# LTC6811_slave_12s_rev4.net
KiCad netlist of a schematic drawn in EAGLE
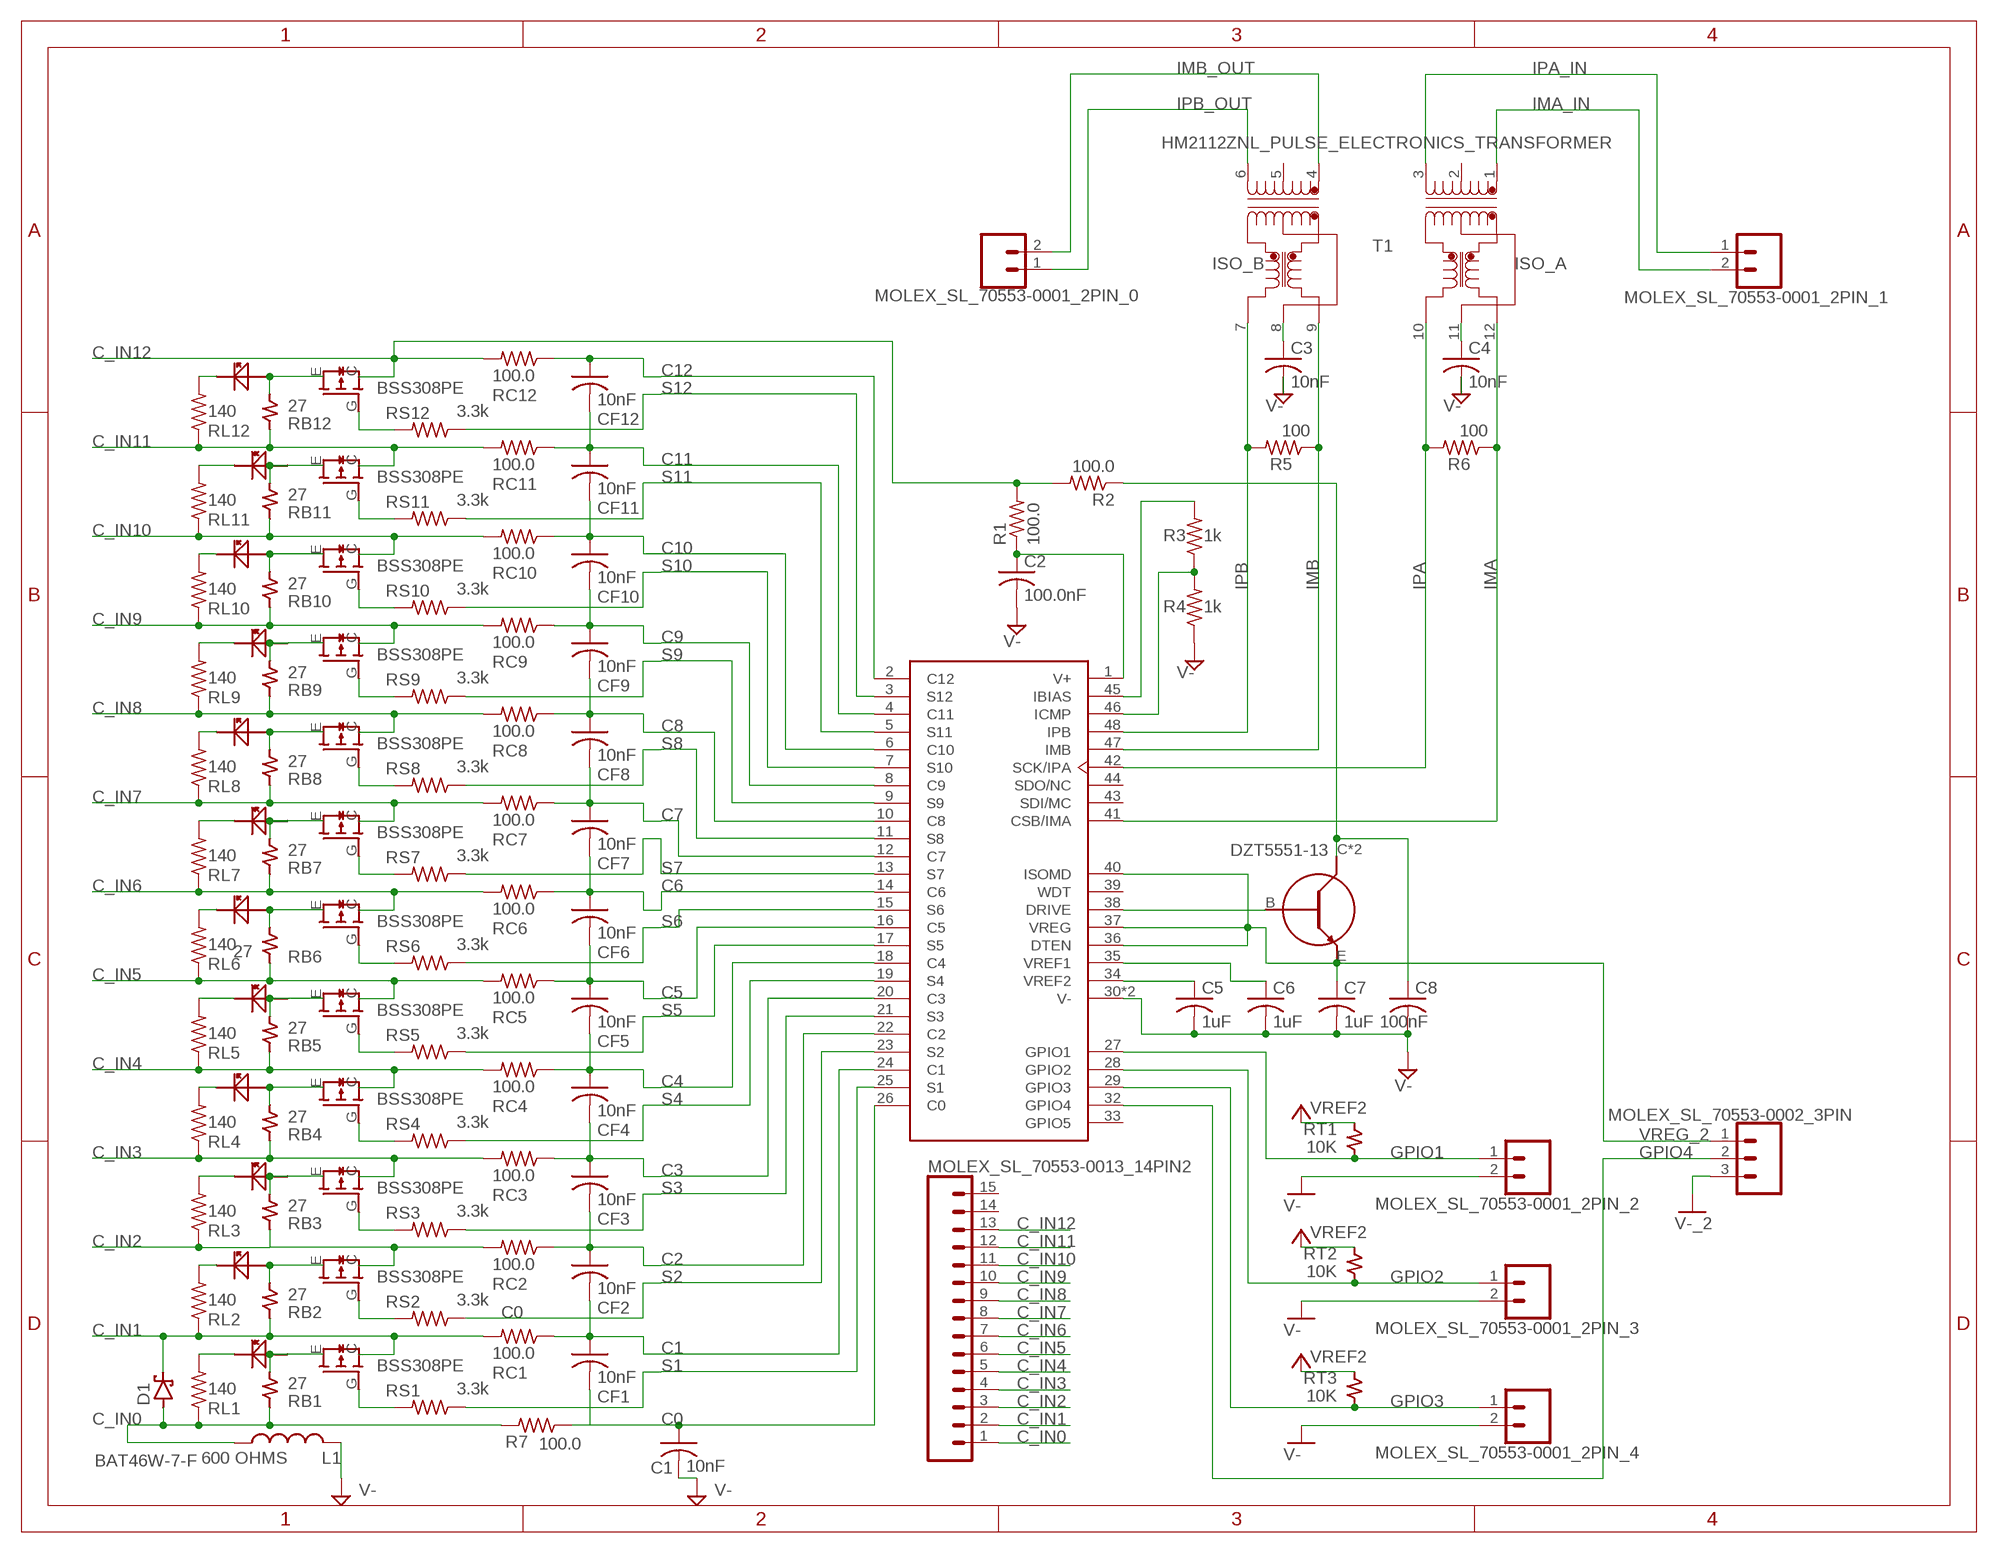
[diagram p0: schematic, sheet 1]

(export (version "E")
  (design (tool "Eeschema 10.0.6"))
  (components
    (comp (ref "C1")
      (value "10nF")
      (footprint "eagle-import:C0805")
      (libsource (lib "eagle-import") (part "C-USC0805"))
    )
    (comp (ref "C2")
      (value "100.0nF")
      (footprint "eagle-import:C0805")
      (libsource (lib "eagle-import") (part "C-USC0805"))
    )
    (comp (ref "C3")
      (value "10nF")
      (footprint "eagle-import:C0805")
      (libsource (lib "eagle-import") (part "C-USC0805"))
    )
    (comp (ref "C4")
      (value "10nF")
      (footprint "eagle-import:C0805")
      (libsource (lib "eagle-import") (part "C-USC0805"))
    )
    (comp (ref "C5")
      (value "1uF")
      (footprint "eagle-import:C0805")
      (libsource (lib "eagle-import") (part "C-USC0805"))
    )
    (comp (ref "C6")
      (value "1uF")
      (footprint "eagle-import:C0805")
      (libsource (lib "eagle-import") (part "C-USC0805"))
    )
    (comp (ref "C7")
      (value "1uF")
      (footprint "eagle-import:C0805")
      (libsource (lib "eagle-import") (part "C-USC0805"))
    )
    (comp (ref "C8")
      (value "100nF")
      (footprint "eagle-import:C0805")
      (libsource (lib "eagle-import") (part "C-USC0805"))
    )
    (comp (ref "CF1")
      (value "10nF")
      (footprint "eagle-import:C0805")
      (libsource (lib "eagle-import") (part "C-USC0805"))
    )
    (comp (ref "CF2")
      (value "10nF")
      (footprint "eagle-import:C0805")
      (libsource (lib "eagle-import") (part "C-USC0805"))
    )
    (comp (ref "CF3")
      (value "10nF")
      (footprint "eagle-import:C0805")
      (libsource (lib "eagle-import") (part "C-USC0805"))
    )
    (comp (ref "CF4")
      (value "10nF")
      (footprint "eagle-import:C0805")
      (libsource (lib "eagle-import") (part "C-USC0805"))
    )
    (comp (ref "CF5")
      (value "10nF")
      (footprint "eagle-import:C0805")
      (libsource (lib "eagle-import") (part "C-USC0805"))
    )
    (comp (ref "CF6")
      (value "10nF")
      (footprint "eagle-import:C0805")
      (libsource (lib "eagle-import") (part "C-USC0805"))
    )
    (comp (ref "CF7")
      (value "10nF")
      (footprint "eagle-import:C0805")
      (libsource (lib "eagle-import") (part "C-USC0805"))
    )
    (comp (ref "CF8")
      (value "10nF")
      (footprint "eagle-import:C0805")
      (libsource (lib "eagle-import") (part "C-USC0805"))
    )
    (comp (ref "CF9")
      (value "10nF")
      (footprint "eagle-import:C0805")
      (libsource (lib "eagle-import") (part "C-USC0805"))
    )
    (comp (ref "CF10")
      (value "10nF")
      (footprint "eagle-import:C0805")
      (libsource (lib "eagle-import") (part "C-USC0805"))
    )
    (comp (ref "CF11")
      (value "10nF")
      (footprint "eagle-import:C0805")
      (libsource (lib "eagle-import") (part "C-USC0805"))
    )
    (comp (ref "CF12")
      (value "10nF")
      (footprint "eagle-import:C0805")
      (libsource (lib "eagle-import") (part "C-USC0805"))
    )
    (comp (ref "D1")
      (value "BAT46W-7-F")
      (footprint "eagle-import:SOD123")
      (libsource (lib "eagle-import") (part "BAT46W-7-F"))
    )
    (comp (ref "L1")
      (value "600 OHMS")
      (footprint "eagle-import:0805_COMPONENT")
      (libsource (lib "eagle-import") (part "0805_FERRITEBEAD_INDUCTOR"))
    )
    (comp (ref "LED1")
      (value "LED_0805")
      (footprint "eagle-import:0805_COMPONENT")
      (libsource (lib "eagle-import") (part "LED_0805"))
    )
    (comp (ref "LED2")
      (value "LED_0805")
      (footprint "eagle-import:0805_COMPONENT")
      (libsource (lib "eagle-import") (part "LED_0805"))
    )
    (comp (ref "LED3")
      (value "LED_0805")
      (footprint "eagle-import:0805_COMPONENT")
      (libsource (lib "eagle-import") (part "LED_0805"))
    )
    (comp (ref "LED4")
      (value "LED_0805")
      (footprint "eagle-import:0805_COMPONENT")
      (libsource (lib "eagle-import") (part "LED_0805"))
    )
    (comp (ref "LED5")
      (value "LED_0805")
      (footprint "eagle-import:0805_COMPONENT")
      (libsource (lib "eagle-import") (part "LED_0805"))
    )
    (comp (ref "LED6")
      (value "LED_0805")
      (footprint "eagle-import:0805_COMPONENT")
      (libsource (lib "eagle-import") (part "LED_0805"))
    )
    (comp (ref "LED7")
      (value "LED_0805")
      (footprint "eagle-import:0805_COMPONENT")
      (libsource (lib "eagle-import") (part "LED_0805"))
    )
    (comp (ref "LED8")
      (value "LED_0805")
      (footprint "eagle-import:0805_COMPONENT")
      (libsource (lib "eagle-import") (part "LED_0805"))
    )
    (comp (ref "LED9")
      (value "LED_0805")
      (footprint "eagle-import:0805_COMPONENT")
      (libsource (lib "eagle-import") (part "LED_0805"))
    )
    (comp (ref "LED10")
      (value "LED_0805")
      (footprint "eagle-import:0805_COMPONENT")
      (libsource (lib "eagle-import") (part "LED_0805"))
    )
    (comp (ref "LED11")
      (value "LED_0805")
      (footprint "eagle-import:0805_COMPONENT")
      (libsource (lib "eagle-import") (part "LED_0805"))
    )
    (comp (ref "LED12")
      (value "LED_0805")
      (footprint "eagle-import:0805_COMPONENT")
      (libsource (lib "eagle-import") (part "LED_0805"))
    )
    (comp (ref "MOLEX_SL_70553-0001_2PIN_0")
      (value "CONN_02")
      (footprint "eagle-import:1X02")
      (libsource (lib "eagle-import") (part "CONN_02"))
    )
    (comp (ref "MOLEX_SL_70553-0001_2PIN_1")
      (value "CONN_02")
      (footprint "eagle-import:1X02")
      (libsource (lib "eagle-import") (part "CONN_02"))
    )
    (comp (ref "MOLEX_SL_70553-0001_2PIN_2")
      (value "CONN_02")
      (footprint "eagle-import:1X02")
      (libsource (lib "eagle-import") (part "CONN_02"))
    )
    (comp (ref "MOLEX_SL_70553-0001_2PIN_3")
      (value "CONN_02")
      (footprint "eagle-import:1X02")
      (libsource (lib "eagle-import") (part "CONN_02"))
    )
    (comp (ref "MOLEX_SL_70553-0001_2PIN_4")
      (value "CONN_02")
      (footprint "eagle-import:1X02")
      (libsource (lib "eagle-import") (part "CONN_02"))
    )
    (comp (ref "MOLEX_SL_70553-0002_3PIN")
      (value "CONN_03")
      (footprint "eagle-import:1X03")
      (libsource (lib "eagle-import") (part "CONN_03"))
    )
    (comp (ref "MOLEX_SL_70553-0013_14PIN2")
      (value "CONN_15")
      (footprint "eagle-import:1X15")
      (libsource (lib "eagle-import") (part "CONN_15"))
    )
    (comp (ref "R1")
      (value "100.0")
      (footprint "eagle-import:R0805")
      (libsource (lib "eagle-import") (part "R-US_R0805"))
    )
    (comp (ref "R2")
      (value "100.0")
      (footprint "eagle-import:R0805")
      (libsource (lib "eagle-import") (part "R-US_R0805"))
    )
    (comp (ref "R3")
      (value "1k")
      (footprint "eagle-import:R0805")
      (libsource (lib "eagle-import") (part "R-US_R0805"))
    )
    (comp (ref "R4")
      (value "1k")
      (footprint "eagle-import:R0805")
      (libsource (lib "eagle-import") (part "R-US_R0805"))
    )
    (comp (ref "R5")
      (value "100")
      (footprint "eagle-import:R0805")
      (libsource (lib "eagle-import") (part "R-US_R0805"))
    )
    (comp (ref "R6")
      (value "100")
      (footprint "eagle-import:R0805")
      (libsource (lib "eagle-import") (part "R-US_R0805"))
    )
    (comp (ref "R7")
      (value "100.0")
      (footprint "eagle-import:R0805")
      (libsource (lib "eagle-import") (part "R-US_R0805"))
    )
    (comp (ref "RB1")
      (value "27")
      (footprint "eagle-import:2817_COMPONENT")
      (libsource (lib "eagle-import") (part "2817_RESISTOR"))
    )
    (comp (ref "RB2")
      (value "27")
      (footprint "eagle-import:2817_COMPONENT")
      (libsource (lib "eagle-import") (part "2817_RESISTOR"))
    )
    (comp (ref "RB3")
      (value "27")
      (footprint "eagle-import:2817_COMPONENT")
      (libsource (lib "eagle-import") (part "2817_RESISTOR"))
    )
    (comp (ref "RB4")
      (value "27")
      (footprint "eagle-import:2817_COMPONENT")
      (libsource (lib "eagle-import") (part "2817_RESISTOR"))
    )
    (comp (ref "RB5")
      (value "27")
      (footprint "eagle-import:2817_COMPONENT")
      (libsource (lib "eagle-import") (part "2817_RESISTOR"))
    )
    (comp (ref "RB6")
      (value "27")
      (footprint "eagle-import:2817_COMPONENT")
      (libsource (lib "eagle-import") (part "2817_RESISTOR"))
    )
    (comp (ref "RB7")
      (value "27")
      (footprint "eagle-import:2817_COMPONENT")
      (libsource (lib "eagle-import") (part "2817_RESISTOR"))
    )
    (comp (ref "RB8")
      (value "27")
      (footprint "eagle-import:2817_COMPONENT")
      (libsource (lib "eagle-import") (part "2817_RESISTOR"))
    )
    (comp (ref "RB9")
      (value "27")
      (footprint "eagle-import:2817_COMPONENT")
      (libsource (lib "eagle-import") (part "2817_RESISTOR"))
    )
    (comp (ref "RB10")
      (value "27")
      (footprint "eagle-import:2817_COMPONENT")
      (libsource (lib "eagle-import") (part "2817_RESISTOR"))
    )
    (comp (ref "RB11")
      (value "27")
      (footprint "eagle-import:2817_COMPONENT")
      (libsource (lib "eagle-import") (part "2817_RESISTOR"))
    )
    (comp (ref "RB12")
      (value "27")
      (footprint "eagle-import:2817_COMPONENT")
      (libsource (lib "eagle-import") (part "2817_RESISTOR"))
    )
    (comp (ref "RC1")
      (value "100.0")
      (footprint "eagle-import:R0805")
      (libsource (lib "eagle-import") (part "R-US_R0805"))
    )
    (comp (ref "RC2")
      (value "100.0")
      (footprint "eagle-import:R0805")
      (libsource (lib "eagle-import") (part "R-US_R0805"))
    )
    (comp (ref "RC3")
      (value "100.0")
      (footprint "eagle-import:R0805")
      (libsource (lib "eagle-import") (part "R-US_R0805"))
    )
    (comp (ref "RC4")
      (value "100.0")
      (footprint "eagle-import:R0805")
      (libsource (lib "eagle-import") (part "R-US_R0805"))
    )
    (comp (ref "RC5")
      (value "100.0")
      (footprint "eagle-import:R0805")
      (libsource (lib "eagle-import") (part "R-US_R0805"))
    )
    (comp (ref "RC6")
      (value "100.0")
      (footprint "eagle-import:R0805")
      (libsource (lib "eagle-import") (part "R-US_R0805"))
    )
    (comp (ref "RC7")
      (value "100.0")
      (footprint "eagle-import:R0805")
      (libsource (lib "eagle-import") (part "R-US_R0805"))
    )
    (comp (ref "RC8")
      (value "100.0")
      (footprint "eagle-import:R0805")
      (libsource (lib "eagle-import") (part "R-US_R0805"))
    )
    (comp (ref "RC9")
      (value "100.0")
      (footprint "eagle-import:R0805")
      (libsource (lib "eagle-import") (part "R-US_R0805"))
    )
    (comp (ref "RC10")
      (value "100.0")
      (footprint "eagle-import:R0805")
      (libsource (lib "eagle-import") (part "R-US_R0805"))
    )
    (comp (ref "RC11")
      (value "100.0")
      (footprint "eagle-import:R0805")
      (libsource (lib "eagle-import") (part "R-US_R0805"))
    )
    (comp (ref "RC12")
      (value "100.0")
      (footprint "eagle-import:R0805")
      (libsource (lib "eagle-import") (part "R-US_R0805"))
    )
    (comp (ref "RL1")
      (value "140")
      (footprint "eagle-import:R0805")
      (libsource (lib "eagle-import") (part "R-US_R0805"))
    )
    (comp (ref "RL2")
      (value "140")
      (footprint "eagle-import:R0805")
      (libsource (lib "eagle-import") (part "R-US_R0805"))
    )
    (comp (ref "RL3")
      (value "140")
      (footprint "eagle-import:R0805")
      (libsource (lib "eagle-import") (part "R-US_R0805"))
    )
    (comp (ref "RL4")
      (value "140")
      (footprint "eagle-import:R0805")
      (libsource (lib "eagle-import") (part "R-US_R0805"))
    )
    (comp (ref "RL5")
      (value "140")
      (footprint "eagle-import:R0805")
      (libsource (lib "eagle-import") (part "R-US_R0805"))
    )
    (comp (ref "RL6")
      (value "140")
      (footprint "eagle-import:R0805")
      (libsource (lib "eagle-import") (part "R-US_R0805"))
    )
    (comp (ref "RL7")
      (value "140")
      (footprint "eagle-import:R0805")
      (libsource (lib "eagle-import") (part "R-US_R0805"))
    )
    (comp (ref "RL8")
      (value "140")
      (footprint "eagle-import:R0805")
      (libsource (lib "eagle-import") (part "R-US_R0805"))
    )
    (comp (ref "RL9")
      (value "140")
      (footprint "eagle-import:R0805")
      (libsource (lib "eagle-import") (part "R-US_R0805"))
    )
    (comp (ref "RL10")
      (value "140")
      (footprint "eagle-import:R0805")
      (libsource (lib "eagle-import") (part "R-US_R0805"))
    )
    (comp (ref "RL11")
      (value "140")
      (footprint "eagle-import:R0805")
      (libsource (lib "eagle-import") (part "R-US_R0805"))
    )
    (comp (ref "RL12")
      (value "140")
      (footprint "eagle-import:R0805")
      (libsource (lib "eagle-import") (part "R-US_R0805"))
    )
    (comp (ref "RS1")
      (value "3.3k")
      (footprint "eagle-import:R0805")
      (libsource (lib "eagle-import") (part "R-US_R0805"))
    )
    (comp (ref "RS2")
      (value "3.3k")
      (footprint "eagle-import:R0805")
      (libsource (lib "eagle-import") (part "R-US_R0805"))
    )
    (comp (ref "RS3")
      (value "3.3k")
      (footprint "eagle-import:R0805")
      (libsource (lib "eagle-import") (part "R-US_R0805"))
    )
    (comp (ref "RS4")
      (value "3.3k")
      (footprint "eagle-import:R0805")
      (libsource (lib "eagle-import") (part "R-US_R0805"))
    )
    (comp (ref "RS5")
      (value "3.3k")
      (footprint "eagle-import:R0805")
      (libsource (lib "eagle-import") (part "R-US_R0805"))
    )
    (comp (ref "RS6")
      (value "3.3k")
      (footprint "eagle-import:R0805")
      (libsource (lib "eagle-import") (part "R-US_R0805"))
    )
    (comp (ref "RS7")
      (value "3.3k")
      (footprint "eagle-import:R0805")
      (libsource (lib "eagle-import") (part "R-US_R0805"))
    )
    (comp (ref "RS8")
      (value "3.3k")
      (footprint "eagle-import:R0805")
      (libsource (lib "eagle-import") (part "R-US_R0805"))
    )
    (comp (ref "RS9")
      (value "3.3k")
      (footprint "eagle-import:R0805")
      (libsource (lib "eagle-import") (part "R-US_R0805"))
    )
    (comp (ref "RS10")
      (value "3.3k")
      (footprint "eagle-import:R0805")
      (libsource (lib "eagle-import") (part "R-US_R0805"))
    )
    (comp (ref "RS11")
      (value "3.3k")
      (footprint "eagle-import:R0805")
      (libsource (lib "eagle-import") (part "R-US_R0805"))
    )
    (comp (ref "RS12")
      (value "3.3k")
      (footprint "eagle-import:R0805")
      (libsource (lib "eagle-import") (part "R-US_R0805"))
    )
    (comp (ref "RT1")
      (value "10K")
      (footprint "eagle-import:0805_RESISTOR")
      (libsource (lib "eagle-import") (part "0805_RESISTOR"))
    )
    (comp (ref "RT2")
      (value "10K")
      (footprint "eagle-import:0805_RESISTOR")
      (libsource (lib "eagle-import") (part "0805_RESISTOR"))
    )
    (comp (ref "RT3")
      (value "10K")
      (footprint "eagle-import:0805_RESISTOR")
      (libsource (lib "eagle-import") (part "0805_RESISTOR"))
    )
    (comp (ref "SW1")
      (value "BSS308PEH6327")
      (footprint "eagle-import:SOT23")
      (libsource (lib "eagle-import") (part "BSS308PEH6327"))
    )
    (comp (ref "SW2")
      (value "BSS308PEH6327")
      (footprint "eagle-import:SOT23")
      (libsource (lib "eagle-import") (part "BSS308PEH6327"))
    )
    (comp (ref "SW3")
      (value "BSS308PEH6327")
      (footprint "eagle-import:SOT23")
      (libsource (lib "eagle-import") (part "BSS308PEH6327"))
    )
    (comp (ref "SW4")
      (value "BSS308PEH6327")
      (footprint "eagle-import:SOT23")
      (libsource (lib "eagle-import") (part "BSS308PEH6327"))
    )
    (comp (ref "SW5")
      (value "BSS308PEH6327")
      (footprint "eagle-import:SOT23")
      (libsource (lib "eagle-import") (part "BSS308PEH6327"))
    )
    (comp (ref "SW6")
      (value "BSS308PEH6327")
      (footprint "eagle-import:SOT23")
      (libsource (lib "eagle-import") (part "BSS308PEH6327"))
    )
    (comp (ref "SW7")
      (value "BSS308PEH6327")
      (footprint "eagle-import:SOT23")
      (libsource (lib "eagle-import") (part "BSS308PEH6327"))
    )
    (comp (ref "SW8")
      (value "BSS308PEH6327")
      (footprint "eagle-import:SOT23")
      (libsource (lib "eagle-import") (part "BSS308PEH6327"))
    )
    (comp (ref "SW9")
      (value "BSS308PEH6327")
      (footprint "eagle-import:SOT23")
      (libsource (lib "eagle-import") (part "BSS308PEH6327"))
    )
    (comp (ref "SW10")
      (value "BSS308PEH6327")
      (footprint "eagle-import:SOT23")
      (libsource (lib "eagle-import") (part "BSS308PEH6327"))
    )
    (comp (ref "SW11")
      (value "BSS308PEH6327")
      (footprint "eagle-import:SOT23")
      (libsource (lib "eagle-import") (part "BSS308PEH6327"))
    )
    (comp (ref "SW12")
      (value "BSS308PEH6327")
      (footprint "eagle-import:SOT23")
      (libsource (lib "eagle-import") (part "BSS308PEH6327"))
    )
    (comp (ref "SW13")
      (value "DZT5551-13")
      (footprint "eagle-import:SOT223-4")
      (libsource (lib "eagle-import") (part "DZT5551-13"))
    )
    (comp (ref "U$3")
      (value "HM2112ZNL_PULSE_ELECTRONICS_TRANSFORMER")
      (footprint "eagle-import:HM2112ZNL_12SMT")
      (libsource (lib "eagle-import") (part "HM2112ZNL_PULSE_ELECTRONICS_TRANSFORMER"))
    )
    (comp (ref "U1")
      (value "LTC6811HG-2#PBF")
      (footprint "eagle-import:LTC6811-1")
      (fields (field (name "MF") "Linear Technology/Analog"))
      (libsource (lib "eagle-import") (part "LTC6811HG-2#PBF"))
    )
  )
  (nets
    (net (code "1") (name "/C0") (class "Default")
      (node (ref "C1") (pin "1") (pinfunction "1_1") (pintype "passive"))
      (node (ref "R7") (pin "1") (pinfunction "1_1") (pintype "passive"))
      (node (ref "U1") (pin "26") (pinfunction "C0_26") (pintype "input"))
    )
    (net (code "2") (name "/C1") (class "Default")
      (node (ref "CF1") (pin "1") (pinfunction "1_1") (pintype "passive"))
      (node (ref "CF2") (pin "2") (pinfunction "2_2") (pintype "passive"))
      (node (ref "RC1") (pin "1") (pinfunction "1_1") (pintype "passive"))
      (node (ref "U1") (pin "24") (pinfunction "C1_24") (pintype "input"))
    )
    (net (code "3") (name "/C2") (class "Default")
      (node (ref "CF2") (pin "1") (pinfunction "1_1") (pintype "passive"))
      (node (ref "CF3") (pin "2") (pinfunction "2_2") (pintype "passive"))
      (node (ref "RC2") (pin "1") (pinfunction "1_1") (pintype "passive"))
      (node (ref "U1") (pin "22") (pinfunction "C2_22") (pintype "input"))
    )
    (net (code "4") (name "/C3") (class "Default")
      (node (ref "CF3") (pin "1") (pinfunction "1_1") (pintype "passive"))
      (node (ref "CF4") (pin "2") (pinfunction "2_2") (pintype "passive"))
      (node (ref "RC3") (pin "1") (pinfunction "1_1") (pintype "passive"))
      (node (ref "U1") (pin "20") (pinfunction "C3_20") (pintype "input"))
    )
    (net (code "5") (name "/C4") (class "Default")
      (node (ref "CF4") (pin "1") (pinfunction "1_1") (pintype "passive"))
      (node (ref "CF5") (pin "2") (pinfunction "2_2") (pintype "passive"))
      (node (ref "RC4") (pin "1") (pinfunction "1_1") (pintype "passive"))
      (node (ref "U1") (pin "18") (pinfunction "C4_18") (pintype "input"))
    )
    (net (code "6") (name "/C5") (class "Default")
      (node (ref "CF5") (pin "1") (pinfunction "1_1") (pintype "passive"))
      (node (ref "CF6") (pin "2") (pinfunction "2_2") (pintype "passive"))
      (node (ref "RC5") (pin "1") (pinfunction "1_1") (pintype "passive"))
      (node (ref "U1") (pin "16") (pinfunction "C5_16") (pintype "input"))
    )
    (net (code "7") (name "/C6") (class "Default")
      (node (ref "CF6") (pin "1") (pinfunction "1_1") (pintype "passive"))
      (node (ref "CF7") (pin "2") (pinfunction "2_2") (pintype "passive"))
      (node (ref "RC6") (pin "1") (pinfunction "1_1") (pintype "passive"))
      (node (ref "U1") (pin "14") (pinfunction "C6_14") (pintype "input"))
    )
    (net (code "8") (name "/C7") (class "Default")
      (node (ref "CF7") (pin "1") (pinfunction "1_1") (pintype "passive"))
      (node (ref "CF8") (pin "2") (pinfunction "2_2") (pintype "passive"))
      (node (ref "RC7") (pin "1") (pinfunction "1_1") (pintype "passive"))
      (node (ref "U1") (pin "12") (pinfunction "C7_12") (pintype "input"))
    )
    (net (code "9") (name "/C8") (class "Default")
      (node (ref "CF8") (pin "1") (pinfunction "1_1") (pintype "passive"))
      (node (ref "CF9") (pin "2") (pinfunction "2_2") (pintype "passive"))
      (node (ref "RC8") (pin "1") (pinfunction "1_1") (pintype "passive"))
      (node (ref "U1") (pin "10") (pinfunction "C8_10") (pintype "input"))
    )
    (net (code "10") (name "/C9") (class "Default")
      (node (ref "CF10") (pin "2") (pinfunction "2_2") (pintype "passive"))
      (node (ref "CF9") (pin "1") (pinfunction "1_1") (pintype "passive"))
      (node (ref "RC9") (pin "1") (pinfunction "1_1") (pintype "passive"))
      (node (ref "U1") (pin "8") (pinfunction "C9_8") (pintype "input"))
    )
    (net (code "11") (name "/C10") (class "Default")
      (node (ref "CF10") (pin "1") (pinfunction "1_1") (pintype "passive"))
      (node (ref "CF11") (pin "2") (pinfunction "2_2") (pintype "passive"))
      (node (ref "RC10") (pin "1") (pinfunction "1_1") (pintype "passive"))
      (node (ref "U1") (pin "6") (pinfunction "C10_6") (pintype "input"))
    )
    (net (code "12") (name "/C11") (class "Default")
      (node (ref "CF11") (pin "1") (pinfunction "1_1") (pintype "passive"))
      (node (ref "CF12") (pin "2") (pinfunction "2_2") (pintype "passive"))
      (node (ref "RC11") (pin "1") (pinfunction "1_1") (pintype "passive"))
      (node (ref "U1") (pin "4") (pinfunction "C11_4") (pintype "input"))
    )
    (net (code "13") (name "/C12") (class "Default")
      (node (ref "CF12") (pin "1") (pinfunction "1_1") (pintype "passive"))
      (node (ref "RC12") (pin "1") (pinfunction "1_1") (pintype "passive"))
      (node (ref "U1") (pin "2") (pinfunction "C12_2") (pintype "input"))
    )
    (net (code "14") (name "/C_IN0") (class "Default")
      (node (ref "D1") (pin "A") (pinfunction "A_A") (pintype "passive"))
      (node (ref "L1") (pin "1") (pinfunction "1_1") (pintype "passive"))
      (node (ref "MOLEX_SL_70553-0013_14PIN2") (pin "1") (pinfunction "1_1") (pintype "passive"))
      (node (ref "R7") (pin "2") (pinfunction "2_2") (pintype "passive"))
      (node (ref "RB1") (pin "2") (pinfunction "P$2_2") (pintype "bidirectional"))
      (node (ref "RL1") (pin "1") (pinfunction "1_1") (pintype "passive"))
    )
    (net (code "15") (name "/C_IN1") (class "Default")
      (node (ref "D1") (pin "C") (pinfunction "C_C") (pintype "passive"))
      (node (ref "MOLEX_SL_70553-0013_14PIN2") (pin "2") (pinfunction "2_2") (pintype "passive"))
      (node (ref "RB2") (pin "2") (pinfunction "P$2_2") (pintype "bidirectional"))
      (node (ref "RC1") (pin "2") (pinfunction "2_2") (pintype "passive"))
      (node (ref "RL2") (pin "1") (pinfunction "1_1") (pintype "passive"))
      (node (ref "SW1") (pin "C") (pinfunction "C_C") (pintype "bidirectional"))
    )
    (net (code "16") (name "/C_IN2") (class "Default")
      (node (ref "MOLEX_SL_70553-0013_14PIN2") (pin "3") (pinfunction "3_3") (pintype "passive"))
      (node (ref "RB3") (pin "2") (pinfunction "P$2_2") (pintype "bidirectional"))
      (node (ref "RC2") (pin "2") (pinfunction "2_2") (pintype "passive"))
      (node (ref "RL3") (pin "1") (pinfunction "1_1") (pintype "passive"))
      (node (ref "SW2") (pin "C") (pinfunction "C_C") (pintype "bidirectional"))
    )
    (net (code "17") (name "/C_IN3") (class "Default")
      (node (ref "MOLEX_SL_70553-0013_14PIN2") (pin "4") (pinfunction "4_4") (pintype "passive"))
      (node (ref "RB4") (pin "2") (pinfunction "P$2_2") (pintype "bidirectional"))
      (node (ref "RC3") (pin "2") (pinfunction "2_2") (pintype "passive"))
      (node (ref "RL4") (pin "1") (pinfunction "1_1") (pintype "passive"))
      (node (ref "SW3") (pin "C") (pinfunction "C_C") (pintype "bidirectional"))
    )
    (net (code "18") (name "/C_IN4") (class "Default")
      (node (ref "MOLEX_SL_70553-0013_14PIN2") (pin "5") (pinfunction "5_5") (pintype "passive"))
      (node (ref "RB5") (pin "2") (pinfunction "P$2_2") (pintype "bidirectional"))
      (node (ref "RC4") (pin "2") (pinfunction "2_2") (pintype "passive"))
      (node (ref "RL5") (pin "1") (pinfunction "1_1") (pintype "passive"))
      (node (ref "SW4") (pin "C") (pinfunction "C_C") (pintype "bidirectional"))
    )
    (net (code "19") (name "/C_IN5") (class "Default")
      (node (ref "MOLEX_SL_70553-0013_14PIN2") (pin "6") (pinfunction "6_6") (pintype "passive"))
      (node (ref "RB6") (pin "2") (pinfunction "P$2_2") (pintype "bidirectional"))
      (node (ref "RC5") (pin "2") (pinfunction "2_2") (pintype "passive"))
      (node (ref "RL6") (pin "1") (pinfunction "1_1") (pintype "passive"))
      (node (ref "SW5") (pin "C") (pinfunction "C_C") (pintype "bidirectional"))
    )
    (net (code "20") (name "/C_IN6") (class "Default")
      (node (ref "MOLEX_SL_70553-0013_14PIN2") (pin "7") (pinfunction "7_7") (pintype "passive"))
      (node (ref "RB7") (pin "2") (pinfunction "P$2_2") (pintype "bidirectional"))
      (node (ref "RC6") (pin "2") (pinfunction "2_2") (pintype "passive"))
      (node (ref "RL7") (pin "1") (pinfunction "1_1") (pintype "passive"))
      (node (ref "SW6") (pin "C") (pinfunction "C_C") (pintype "bidirectional"))
    )
    (net (code "21") (name "/C_IN7") (class "Default")
      (node (ref "MOLEX_SL_70553-0013_14PIN2") (pin "8") (pinfunction "8_8") (pintype "passive"))
      (node (ref "RB8") (pin "2") (pinfunction "P$2_2") (pintype "bidirectional"))
      (node (ref "RC7") (pin "2") (pinfunction "2_2") (pintype "passive"))
      (node (ref "RL8") (pin "1") (pinfunction "1_1") (pintype "passive"))
      (node (ref "SW7") (pin "C") (pinfunction "C_C") (pintype "bidirectional"))
    )
    (net (code "22") (name "/C_IN8") (class "Default")
      (node (ref "MOLEX_SL_70553-0013_14PIN2") (pin "9") (pinfunction "9_9") (pintype "passive"))
      (node (ref "RB9") (pin "2") (pinfunction "P$2_2") (pintype "bidirectional"))
      (node (ref "RC8") (pin "2") (pinfunction "2_2") (pintype "passive"))
      (node (ref "RL9") (pin "1") (pinfunction "1_1") (pintype "passive"))
      (node (ref "SW8") (pin "C") (pinfunction "C_C") (pintype "bidirectional"))
    )
    (net (code "23") (name "/C_IN9") (class "Default")
      (node (ref "MOLEX_SL_70553-0013_14PIN2") (pin "10") (pinfunction "10_10") (pintype "passive"))
      (node (ref "RB10") (pin "2") (pinfunction "P$2_2") (pintype "bidirectional"))
      (node (ref "RC9") (pin "2") (pinfunction "2_2") (pintype "passive"))
      (node (ref "RL10") (pin "1") (pinfunction "1_1") (pintype "passive"))
      (node (ref "SW9") (pin "C") (pinfunction "C_C") (pintype "bidirectional"))
    )
    (net (code "24") (name "/C_IN10") (class "Default")
      (node (ref "MOLEX_SL_70553-0013_14PIN2") (pin "11") (pinfunction "11_11") (pintype "passive"))
      (node (ref "RB11") (pin "2") (pinfunction "P$2_2") (pintype "bidirectional"))
      (node (ref "RC10") (pin "2") (pinfunction "2_2") (pintype "passive"))
      (node (ref "RL11") (pin "1") (pinfunction "1_1") (pintype "passive"))
      (node (ref "SW10") (pin "C") (pinfunction "C_C") (pintype "bidirectional"))
    )
    (net (code "25") (name "/C_IN11") (class "Default")
      (node (ref "MOLEX_SL_70553-0013_14PIN2") (pin "12") (pinfunction "12_12") (pintype "passive"))
      (node (ref "RB12") (pin "2") (pinfunction "P$2_2") (pintype "bidirectional"))
      (node (ref "RC11") (pin "2") (pinfunction "2_2") (pintype "passive"))
      (node (ref "RL12") (pin "1") (pinfunction "1_1") (pintype "passive"))
      (node (ref "SW11") (pin "C") (pinfunction "C_C") (pintype "bidirectional"))
    )
    (net (code "26") (name "/C_IN12") (class "Default")
      (node (ref "MOLEX_SL_70553-0013_14PIN2") (pin "13") (pinfunction "13_13") (pintype "passive"))
      (node (ref "R1") (pin "2") (pinfunction "2_2") (pintype "passive"))
      (node (ref "R2") (pin "2") (pinfunction "2_2") (pintype "passive"))
      (node (ref "RC12") (pin "2") (pinfunction "2_2") (pintype "passive"))
      (node (ref "SW12") (pin "C") (pinfunction "C_C") (pintype "bidirectional"))
    )
    (net (code "27") (name "/GPIO1") (class "Default")
      (node (ref "MOLEX_SL_70553-0001_2PIN_2") (pin "1") (pinfunction "1_1") (pintype "passive"))
      (node (ref "RT1") (pin "P$2") (pinfunction "P$2_P$2") (pintype "bidirectional"))
      (node (ref "U1") (pin "27") (pinfunction "GPIO1_27") (pintype "bidirectional"))
    )
    (net (code "28") (name "/GPIO2") (class "Default")
      (node (ref "MOLEX_SL_70553-0001_2PIN_3") (pin "1") (pinfunction "1_1") (pintype "passive"))
      (node (ref "RT2") (pin "P$2") (pinfunction "P$2_P$2") (pintype "bidirectional"))
      (node (ref "U1") (pin "28") (pinfunction "GPIO2_28") (pintype "bidirectional"))
    )
    (net (code "29") (name "/GPIO3") (class "Default")
      (node (ref "MOLEX_SL_70553-0001_2PIN_4") (pin "1") (pinfunction "1_1") (pintype "passive"))
      (node (ref "RT3") (pin "P$2") (pinfunction "P$2_P$2") (pintype "bidirectional"))
      (node (ref "U1") (pin "29") (pinfunction "GPIO3_29") (pintype "bidirectional"))
    )
    (net (code "30") (name "/GPIO4") (class "Default")
      (node (ref "MOLEX_SL_70553-0002_3PIN") (pin "2") (pinfunction "2_2") (pintype "passive"))
      (node (ref "U1") (pin "32") (pinfunction "GPIO4_32") (pintype "bidirectional"))
    )
    (net (code "31") (name "/IMA") (class "Default")
      (node (ref "R6") (pin "1") (pinfunction "1_1") (pintype "passive"))
      (node (ref "U$3") (pin "12") (pinfunction "12_12") (pintype "bidirectional"))
      (node (ref "U1") (pin "41") (pinfunction "CSB/IMA_41") (pintype "input"))
    )
    (net (code "32") (name "/IMA_IN") (class "Default")
      (node (ref "MOLEX_SL_70553-0001_2PIN_1") (pin "2") (pinfunction "2_2") (pintype "passive"))
      (node (ref "U$3") (pin "1") (pinfunction "1_1") (pintype "bidirectional"))
    )
    (net (code "33") (name "/IMB") (class "Default")
      (node (ref "R5") (pin "1") (pinfunction "1_1") (pintype "passive"))
      (node (ref "U$3") (pin "9") (pinfunction "9_9") (pintype "bidirectional"))
      (node (ref "U1") (pin "47") (pinfunction "IMB_47") (pintype "input"))
    )
    (net (code "34") (name "/IMB_OUT") (class "Default")
      (node (ref "MOLEX_SL_70553-0001_2PIN_0") (pin "2") (pinfunction "2_2") (pintype "passive"))
      (node (ref "U$3") (pin "4") (pinfunction "4_4") (pintype "bidirectional"))
    )
    (net (code "35") (name "/IPA") (class "Default")
      (node (ref "R6") (pin "2") (pinfunction "2_2") (pintype "passive"))
      (node (ref "U$3") (pin "10") (pinfunction "10_10") (pintype "bidirectional"))
      (node (ref "U1") (pin "42") (pinfunction "SCK/IPA_42") (pintype "input"))
    )
    (net (code "36") (name "/IPA_IN") (class "Default")
      (node (ref "MOLEX_SL_70553-0001_2PIN_1") (pin "1") (pinfunction "1_1") (pintype "passive"))
      (node (ref "U$3") (pin "3") (pinfunction "3_3") (pintype "bidirectional"))
    )
    (net (code "37") (name "/IPB") (class "Default")
      (node (ref "R5") (pin "2") (pinfunction "2_2") (pintype "passive"))
      (node (ref "U$3") (pin "7") (pinfunction "7_7") (pintype "bidirectional"))
      (node (ref "U1") (pin "48") (pinfunction "IPB_48") (pintype "input"))
    )
    (net (code "38") (name "/IPB_OUT") (class "Default")
      (node (ref "MOLEX_SL_70553-0001_2PIN_0") (pin "1") (pinfunction "1_1") (pintype "passive"))
      (node (ref "U$3") (pin "6") (pinfunction "6_6") (pintype "bidirectional"))
    )
    (net (code "39") (name "/S1") (class "Default")
      (node (ref "RS1") (pin "1") (pinfunction "1_1") (pintype "passive"))
      (node (ref "U1") (pin "25") (pinfunction "S1_25") (pintype "bidirectional"))
    )
    (net (code "40") (name "/S2") (class "Default")
      (node (ref "RS2") (pin "1") (pinfunction "1_1") (pintype "passive"))
      (node (ref "U1") (pin "23") (pinfunction "S2_23") (pintype "bidirectional"))
    )
    (net (code "41") (name "/S3") (class "Default")
      (node (ref "RS3") (pin "1") (pinfunction "1_1") (pintype "passive"))
      (node (ref "U1") (pin "21") (pinfunction "S3_21") (pintype "bidirectional"))
    )
    (net (code "42") (name "/S4") (class "Default")
      (node (ref "RS4") (pin "1") (pinfunction "1_1") (pintype "passive"))
      (node (ref "U1") (pin "19") (pinfunction "S4_19") (pintype "bidirectional"))
    )
    (net (code "43") (name "/S5") (class "Default")
      (node (ref "RS5") (pin "1") (pinfunction "1_1") (pintype "passive"))
      (node (ref "U1") (pin "17") (pinfunction "S5_17") (pintype "bidirectional"))
    )
    (net (code "44") (name "/S6") (class "Default")
      (node (ref "RS6") (pin "1") (pinfunction "1_1") (pintype "passive"))
      (node (ref "U1") (pin "15") (pinfunction "S6_15") (pintype "bidirectional"))
    )
    (net (code "45") (name "/S7") (class "Default")
      (node (ref "RS7") (pin "1") (pinfunction "1_1") (pintype "passive"))
      (node (ref "U1") (pin "13") (pinfunction "S7_13") (pintype "bidirectional"))
    )
    (net (code "46") (name "/S8") (class "Default")
      (node (ref "RS8") (pin "1") (pinfunction "1_1") (pintype "passive"))
      (node (ref "U1") (pin "11") (pinfunction "S8_11") (pintype "bidirectional"))
    )
    (net (code "47") (name "/S9") (class "Default")
      (node (ref "RS9") (pin "1") (pinfunction "1_1") (pintype "passive"))
      (node (ref "U1") (pin "9") (pinfunction "S9_9") (pintype "bidirectional"))
    )
    (net (code "48") (name "/S10") (class "Default")
      (node (ref "RS10") (pin "1") (pinfunction "1_1") (pintype "passive"))
      (node (ref "U1") (pin "7") (pinfunction "S10_7") (pintype "bidirectional"))
    )
    (net (code "49") (name "/S11") (class "Default")
      (node (ref "RS11") (pin "1") (pinfunction "1_1") (pintype "passive"))
      (node (ref "U1") (pin "5") (pinfunction "S11_5") (pintype "bidirectional"))
    )
    (net (code "50") (name "/S12") (class "Default")
      (node (ref "RS12") (pin "1") (pinfunction "1_1") (pintype "passive"))
      (node (ref "U1") (pin "3") (pinfunction "S12_3") (pintype "bidirectional"))
    )
    (net (code "51") (name "/VREG_2") (class "Default")
      (node (ref "C7") (pin "1") (pinfunction "1_1") (pintype "passive"))
      (node (ref "MOLEX_SL_70553-0002_3PIN") (pin "1") (pinfunction "1_1") (pintype "passive"))
      (node (ref "SW13") (pin "E") (pinfunction "E_E") (pintype "bidirectional"))
      (node (ref "U1") (pin "36") (pinfunction "DTEN_36") (pintype "input"))
      (node (ref "U1") (pin "37") (pinfunction "VREG_37") (pintype "power_in"))
      (node (ref "U1") (pin "40") (pinfunction "ISOMD_40") (pintype "input"))
    )
    (net (code "52") (name "GND") (class "Default")
      (node (ref "C1") (pin "2") (pinfunction "2_2") (pintype "passive"))
      (node (ref "C2") (pin "2") (pinfunction "2_2") (pintype "passive"))
      (node (ref "C3") (pin "2") (pinfunction "2_2") (pintype "passive"))
      (node (ref "C4") (pin "2") (pinfunction "2_2") (pintype "passive"))
      (node (ref "C5") (pin "2") (pinfunction "2_2") (pintype "passive"))
      (node (ref "C6") (pin "2") (pinfunction "2_2") (pintype "passive"))
      (node (ref "C7") (pin "2") (pinfunction "2_2") (pintype "passive"))
      (node (ref "C8") (pin "2") (pinfunction "2_2") (pintype "passive"))
      (node (ref "L1") (pin "2") (pinfunction "2_2") (pintype "passive"))
      (node (ref "MOLEX_SL_70553-0001_2PIN_2") (pin "2") (pinfunction "2_2") (pintype "passive"))
      (node (ref "MOLEX_SL_70553-0001_2PIN_3") (pin "2") (pinfunction "2_2") (pintype "passive"))
      (node (ref "MOLEX_SL_70553-0001_2PIN_4") (pin "2") (pinfunction "2_2") (pintype "passive"))
      (node (ref "MOLEX_SL_70553-0002_3PIN") (pin "3") (pinfunction "3_3") (pintype "passive"))
      (node (ref "R4") (pin "1") (pinfunction "1_1") (pintype "passive"))
      (node (ref "U1") (pin "30") (pinfunction "V-_30") (pintype "power_in"))
      (node (ref "U1") (pin "31") (pinfunction "V-_31") (pintype "power_in"))
    )
    (net (code "53") (name "Net-(C3-Pad1)") (class "Default")
      (node (ref "C3") (pin "1") (pinfunction "1_1") (pintype "passive"))
      (node (ref "U$3") (pin "8") (pinfunction "8_8") (pintype "bidirectional"))
    )
    (net (code "54") (name "Net-(C4-Pad1)") (class "Default")
      (node (ref "C4") (pin "1") (pinfunction "1_1") (pintype "passive"))
      (node (ref "U$3") (pin "11") (pinfunction "11_11") (pintype "bidirectional"))
    )
    (net (code "55") (name "Net-(C8-Pad1)") (class "Default")
      (node (ref "C8") (pin "1") (pinfunction "1_1") (pintype "passive"))
      (node (ref "R2") (pin "1") (pinfunction "1_1") (pintype "passive"))
      (node (ref "SW13") (pin "C") (pinfunction "C_C") (pintype "bidirectional"))
      (node (ref "SW13") (pin "C@2") (pinfunction "C_C@2") (pintype "bidirectional"))
    )
    (net (code "56") (name "Net-(LED1-P$1)") (class "Default")
      (node (ref "LED1") (pin "1") (pinfunction "P$1_1") (pintype "bidirectional"))
      (node (ref "RL1") (pin "2") (pinfunction "2_2") (pintype "passive"))
    )
    (net (code "57") (name "Net-(LED1-P$2)") (class "Default")
      (node (ref "LED1") (pin "2") (pinfunction "P$2_2") (pintype "bidirectional"))
      (node (ref "RB1") (pin "1") (pinfunction "P$1_1") (pintype "bidirectional"))
      (node (ref "SW1") (pin "E") (pinfunction "E_E") (pintype "bidirectional"))
    )
    (net (code "58") (name "Net-(LED2-P$1)") (class "Default")
      (node (ref "LED2") (pin "1") (pinfunction "P$1_1") (pintype "bidirectional"))
      (node (ref "RL2") (pin "2") (pinfunction "2_2") (pintype "passive"))
    )
    (net (code "59") (name "Net-(LED2-P$2)") (class "Default")
      (node (ref "LED2") (pin "2") (pinfunction "P$2_2") (pintype "bidirectional"))
      (node (ref "RB2") (pin "1") (pinfunction "P$1_1") (pintype "bidirectional"))
      (node (ref "SW2") (pin "E") (pinfunction "E_E") (pintype "bidirectional"))
    )
    (net (code "60") (name "Net-(LED3-P$1)") (class "Default")
      (node (ref "LED3") (pin "1") (pinfunction "P$1_1") (pintype "bidirectional"))
      (node (ref "RL3") (pin "2") (pinfunction "2_2") (pintype "passive"))
    )
    (net (code "61") (name "Net-(LED3-P$2)") (class "Default")
      (node (ref "LED3") (pin "2") (pinfunction "P$2_2") (pintype "bidirectional"))
      (node (ref "RB3") (pin "1") (pinfunction "P$1_1") (pintype "bidirectional"))
      (node (ref "SW3") (pin "E") (pinfunction "E_E") (pintype "bidirectional"))
    )
    (net (code "62") (name "Net-(LED4-P$1)") (class "Default")
      (node (ref "LED4") (pin "1") (pinfunction "P$1_1") (pintype "bidirectional"))
      (node (ref "RL4") (pin "2") (pinfunction "2_2") (pintype "passive"))
    )
    (net (code "63") (name "Net-(LED4-P$2)") (class "Default")
      (node (ref "LED4") (pin "2") (pinfunction "P$2_2") (pintype "bidirectional"))
      (node (ref "RB4") (pin "1") (pinfunction "P$1_1") (pintype "bidirectional"))
      (node (ref "SW4") (pin "E") (pinfunction "E_E") (pintype "bidirectional"))
    )
    (net (code "64") (name "Net-(LED5-P$1)") (class "Default")
      (node (ref "LED5") (pin "1") (pinfunction "P$1_1") (pintype "bidirectional"))
      (node (ref "RL5") (pin "2") (pinfunction "2_2") (pintype "passive"))
    )
    (net (code "65") (name "Net-(LED5-P$2)") (class "Default")
      (node (ref "LED5") (pin "2") (pinfunction "P$2_2") (pintype "bidirectional"))
      (node (ref "RB5") (pin "1") (pinfunction "P$1_1") (pintype "bidirectional"))
      (node (ref "SW5") (pin "E") (pinfunction "E_E") (pintype "bidirectional"))
    )
    (net (code "66") (name "Net-(LED6-P$1)") (class "Default")
      (node (ref "LED6") (pin "1") (pinfunction "P$1_1") (pintype "bidirectional"))
      (node (ref "RL6") (pin "2") (pinfunction "2_2") (pintype "passive"))
    )
    (net (code "67") (name "Net-(LED6-P$2)") (class "Default")
      (node (ref "LED6") (pin "2") (pinfunction "P$2_2") (pintype "bidirectional"))
      (node (ref "RB6") (pin "1") (pinfunction "P$1_1") (pintype "bidirectional"))
      (node (ref "SW6") (pin "E") (pinfunction "E_E") (pintype "bidirectional"))
    )
    (net (code "68") (name "Net-(LED7-P$1)") (class "Default")
      (node (ref "LED7") (pin "1") (pinfunction "P$1_1") (pintype "bidirectional"))
      (node (ref "RL7") (pin "2") (pinfunction "2_2") (pintype "passive"))
    )
    (net (code "69") (name "Net-(LED7-P$2)") (class "Default")
      (node (ref "LED7") (pin "2") (pinfunction "P$2_2") (pintype "bidirectional"))
      (node (ref "RB7") (pin "1") (pinfunction "P$1_1") (pintype "bidirectional"))
      (node (ref "SW7") (pin "E") (pinfunction "E_E") (pintype "bidirectional"))
    )
    (net (code "70") (name "Net-(LED8-P$1)") (class "Default")
      (node (ref "LED8") (pin "1") (pinfunction "P$1_1") (pintype "bidirectional"))
      (node (ref "RL8") (pin "2") (pinfunction "2_2") (pintype "passive"))
    )
    (net (code "71") (name "Net-(LED8-P$2)") (class "Default")
      (node (ref "LED8") (pin "2") (pinfunction "P$2_2") (pintype "bidirectional"))
      (node (ref "RB8") (pin "1") (pinfunction "P$1_1") (pintype "bidirectional"))
      (node (ref "SW8") (pin "E") (pinfunction "E_E") (pintype "bidirectional"))
    )
    (net (code "72") (name "Net-(LED9-P$1)") (class "Default")
      (node (ref "LED9") (pin "1") (pinfunction "P$1_1") (pintype "bidirectional"))
      (node (ref "RL9") (pin "2") (pinfunction "2_2") (pintype "passive"))
    )
    (net (code "73") (name "Net-(LED9-P$2)") (class "Default")
      (node (ref "LED9") (pin "2") (pinfunction "P$2_2") (pintype "bidirectional"))
      (node (ref "RB9") (pin "1") (pinfunction "P$1_1") (pintype "bidirectional"))
      (node (ref "SW9") (pin "E") (pinfunction "E_E") (pintype "bidirectional"))
    )
    (net (code "74") (name "Net-(LED10-P$1)") (class "Default")
      (node (ref "LED10") (pin "1") (pinfunction "P$1_1") (pintype "bidirectional"))
      (node (ref "RL10") (pin "2") (pinfunction "2_2") (pintype "passive"))
    )
    (net (code "75") (name "Net-(LED10-P$2)") (class "Default")
      (node (ref "LED10") (pin "2") (pinfunction "P$2_2") (pintype "bidirectional"))
      (node (ref "RB10") (pin "1") (pinfunction "P$1_1") (pintype "bidirectional"))
      (node (ref "SW10") (pin "E") (pinfunction "E_E") (pintype "bidirectional"))
    )
    (net (code "76") (name "Net-(LED11-P$1)") (class "Default")
      (node (ref "LED11") (pin "1") (pinfunction "P$1_1") (pintype "bidirectional"))
      (node (ref "RL11") (pin "2") (pinfunction "2_2") (pintype "passive"))
    )
    (net (code "77") (name "Net-(LED11-P$2)") (class "Default")
      (node (ref "LED11") (pin "2") (pinfunction "P$2_2") (pintype "bidirectional"))
      (node (ref "RB11") (pin "1") (pinfunction "P$1_1") (pintype "bidirectional"))
      (node (ref "SW11") (pin "E") (pinfunction "E_E") (pintype "bidirectional"))
    )
    (net (code "78") (name "Net-(LED12-P$1)") (class "Default")
      (node (ref "LED12") (pin "1") (pinfunction "P$1_1") (pintype "bidirectional"))
      (node (ref "RL12") (pin "2") (pinfunction "2_2") (pintype "passive"))
    )
    (net (code "79") (name "Net-(LED12-P$2)") (class "Default")
      (node (ref "LED12") (pin "2") (pinfunction "P$2_2") (pintype "bidirectional"))
      (node (ref "RB12") (pin "1") (pinfunction "P$1_1") (pintype "bidirectional"))
      (node (ref "SW12") (pin "E") (pinfunction "E_E") (pintype "bidirectional"))
    )
    (net (code "80") (name "Net-(SW1-B)") (class "Default")
      (node (ref "RS1") (pin "2") (pinfunction "2_2") (pintype "passive"))
      (node (ref "SW1") (pin "G") (pinfunction "B_G") (pintype "bidirectional"))
    )
    (net (code "81") (name "Net-(SW2-B)") (class "Default")
      (node (ref "RS2") (pin "2") (pinfunction "2_2") (pintype "passive"))
      (node (ref "SW2") (pin "G") (pinfunction "B_G") (pintype "bidirectional"))
    )
    (net (code "82") (name "Net-(SW3-B)") (class "Default")
      (node (ref "RS3") (pin "2") (pinfunction "2_2") (pintype "passive"))
      (node (ref "SW3") (pin "G") (pinfunction "B_G") (pintype "bidirectional"))
    )
    (net (code "83") (name "Net-(SW4-B)") (class "Default")
      (node (ref "RS4") (pin "2") (pinfunction "2_2") (pintype "passive"))
      (node (ref "SW4") (pin "G") (pinfunction "B_G") (pintype "bidirectional"))
    )
    (net (code "84") (name "Net-(SW5-B)") (class "Default")
      (node (ref "RS5") (pin "2") (pinfunction "2_2") (pintype "passive"))
      (node (ref "SW5") (pin "G") (pinfunction "B_G") (pintype "bidirectional"))
    )
    (net (code "85") (name "Net-(SW6-B)") (class "Default")
      (node (ref "RS6") (pin "2") (pinfunction "2_2") (pintype "passive"))
      (node (ref "SW6") (pin "G") (pinfunction "B_G") (pintype "bidirectional"))
    )
    (net (code "86") (name "Net-(SW7-B)") (class "Default")
      (node (ref "RS7") (pin "2") (pinfunction "2_2") (pintype "passive"))
      (node (ref "SW7") (pin "G") (pinfunction "B_G") (pintype "bidirectional"))
    )
    (net (code "87") (name "Net-(SW8-B)") (class "Default")
      (node (ref "RS8") (pin "2") (pinfunction "2_2") (pintype "passive"))
      (node (ref "SW8") (pin "G") (pinfunction "B_G") (pintype "bidirectional"))
    )
    (net (code "88") (name "Net-(SW9-B)") (class "Default")
      (node (ref "RS9") (pin "2") (pinfunction "2_2") (pintype "passive"))
      (node (ref "SW9") (pin "G") (pinfunction "B_G") (pintype "bidirectional"))
    )
    (net (code "89") (name "Net-(SW10-B)") (class "Default")
      (node (ref "RS10") (pin "2") (pinfunction "2_2") (pintype "passive"))
      (node (ref "SW10") (pin "G") (pinfunction "B_G") (pintype "bidirectional"))
    )
    (net (code "90") (name "Net-(SW11-B)") (class "Default")
      (node (ref "RS11") (pin "2") (pinfunction "2_2") (pintype "passive"))
      (node (ref "SW11") (pin "G") (pinfunction "B_G") (pintype "bidirectional"))
    )
    (net (code "91") (name "Net-(SW12-B)") (class "Default")
      (node (ref "RS12") (pin "2") (pinfunction "2_2") (pintype "passive"))
      (node (ref "SW12") (pin "G") (pinfunction "B_G") (pintype "bidirectional"))
    )
    (net (code "92") (name "Net-(U1-DRIVE)") (class "Default")
      (node (ref "SW13") (pin "B") (pinfunction "B_B") (pintype "bidirectional"))
      (node (ref "U1") (pin "38") (pinfunction "DRIVE_38") (pintype "output"))
    )
    (net (code "93") (name "Net-(U1-IBIAS)") (class "Default")
      (node (ref "R3") (pin "2") (pinfunction "2_2") (pintype "passive"))
      (node (ref "U1") (pin "45") (pinfunction "IBIAS_45") (pintype "input"))
    )
    (net (code "94") (name "Net-(U1-ICMP)") (class "Default")
      (node (ref "R3") (pin "1") (pinfunction "1_1") (pintype "passive"))
      (node (ref "R4") (pin "2") (pinfunction "2_2") (pintype "passive"))
      (node (ref "U1") (pin "46") (pinfunction "ICMP_46") (pintype "input"))
    )
    (net (code "95") (name "Net-(U1-V+)") (class "Default")
      (node (ref "C2") (pin "1") (pinfunction "1_1") (pintype "passive"))
      (node (ref "R1") (pin "1") (pinfunction "1_1") (pintype "passive"))
      (node (ref "U1") (pin "1") (pinfunction "V+_1") (pintype "power_in"))
    )
    (net (code "96") (name "Net-(U1-VREF1)") (class "Default")
      (node (ref "C6") (pin "1") (pinfunction "1_1") (pintype "passive"))
      (node (ref "U1") (pin "35") (pinfunction "VREF1_35") (pintype "power_in"))
    )
    (net (code "97") (name "VREF2") (class "Default")
      (node (ref "C5") (pin "1") (pinfunction "1_1") (pintype "passive"))
      (node (ref "RT1") (pin "P$1") (pinfunction "P$1_P$1") (pintype "bidirectional"))
      (node (ref "RT2") (pin "P$1") (pinfunction "P$1_P$1") (pintype "bidirectional"))
      (node (ref "RT3") (pin "P$1") (pinfunction "P$1_P$1") (pintype "bidirectional"))
      (node (ref "U1") (pin "34") (pinfunction "VREF2_34") (pintype "power_in"))
    )
    (net (code "98") (name "unconnected-(CF1-Pad2)") (class "Default")
      (node (ref "CF1") (pin "2") (pinfunction "2_2") (pintype "passive"))
    )
    (net (code "99") (name "unconnected-(MOLEX_SL_70553-0013_14PIN2-Pad14)") (class "Default")
      (node (ref "MOLEX_SL_70553-0013_14PIN2") (pin "14") (pinfunction "14_14") (pintype "passive"))
    )
    (net (code "100") (name "unconnected-(MOLEX_SL_70553-0013_14PIN2-Pad15)") (class "Default")
      (node (ref "MOLEX_SL_70553-0013_14PIN2") (pin "15") (pinfunction "15_15") (pintype "passive"))
    )
    (net (code "101") (name "unconnected-(U$3-Pad2)") (class "Default")
      (node (ref "U$3") (pin "2") (pinfunction "2_2") (pintype "bidirectional"))
    )
    (net (code "102") (name "unconnected-(U$3-Pad5)") (class "Default")
      (node (ref "U$3") (pin "5") (pinfunction "5_5") (pintype "bidirectional"))
    )
    (net (code "103") (name "unconnected-(U1-GPIO5-Pad33)") (class "Default")
      (node (ref "U1") (pin "33") (pinfunction "GPIO5_33") (pintype "bidirectional"))
    )
    (net (code "104") (name "unconnected-(U1-SDI{slash}MC-Pad43)") (class "Default")
      (node (ref "U1") (pin "43") (pinfunction "SDI/MC_43") (pintype "input"))
    )
    (net (code "105") (name "unconnected-(U1-SDO{slash}NC-Pad44)") (class "Default")
      (node (ref "U1") (pin "44") (pinfunction "SDO/NC_44") (pintype "output"))
    )
    (net (code "106") (name "unconnected-(U1-WDT-Pad39)") (class "Default")
      (node (ref "U1") (pin "39") (pinfunction "WDT_39") (pintype "output"))
    )
  )
)
